# Fleet-Monitor-Overview.net
KiCad netlist of a schematic drawn in Altium Designer
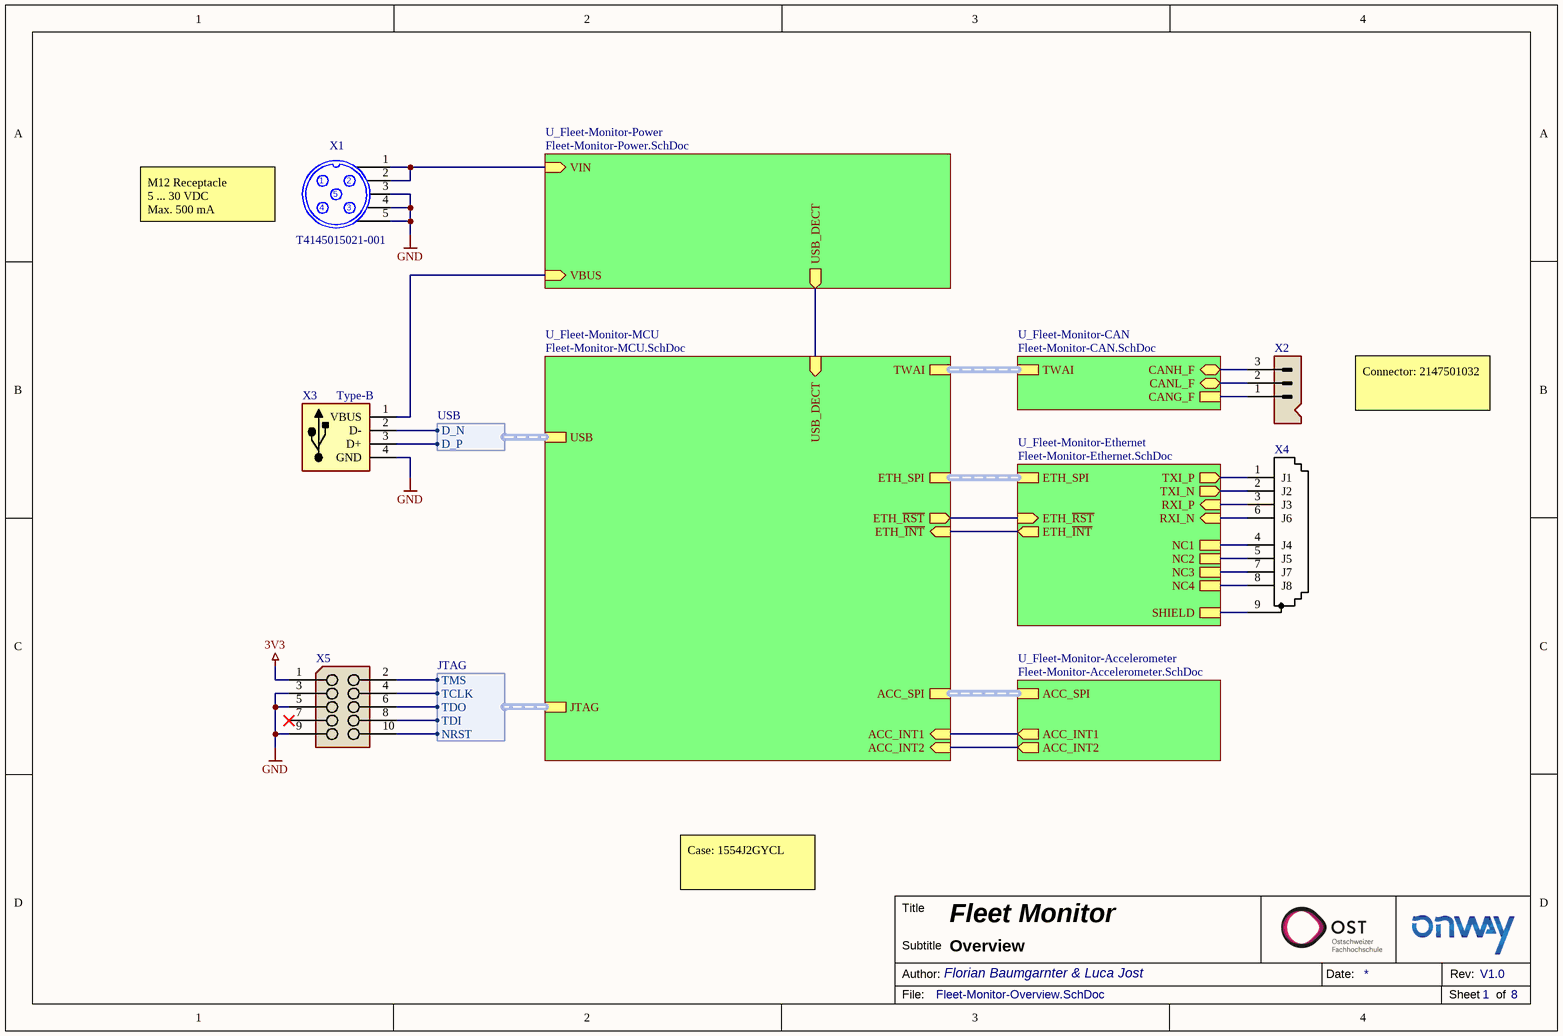
[diagram p0: Fleet-Monitor-Overview.SchDoc]

(export (version "E")
  (design (tool "Eeschema 10.0.6"))
  (components
    (comp (ref "X1")
      (value "T4145015021-001")
      (footprint "THT Connector M12")
      (description "M12 Receptacle Connector PCB Assembly")
      (libsource (lib "Fleet-Monitor") (part "T4145015021"))
    )
    (comp (ref "X2")
      (value "Pin Header Through Hole Wire To Board")
      (footprint "THT Connector 0436500315")
      (libsource (lib "Fleet-Monitor") (part "X-Stiftleiste (3-Fach)"))
    )
    (comp (ref "X3")
      (value "Type-B")
      (footprint "THT Connector MUSBD111M5")
      (description "Typ-B")
      (libsource (lib "Fleet-Monitor") (part "X-USB-Buchse"))
    )
    (comp (ref "X4")
      (value "NE8FDH-C5E-TOP")
      (footprint "THT Connector NE8FDH-C5E-TOP")
      (description "RJ45 etherCON IP65")
      (libsource (lib "Fleet-Monitor") (part "NE8FDH-C5E-TOP"))
    )
    (comp (ref "X5")
      (value "JTAG-Header (ARM-Cortex)")
      (footprint "SMD Connector 1.27mm (2x5)")
      (libsource (lib "Custom ST-Link Old") (part "X-JTAG-Header (ARM-Cortex)"))
    )
  )
  (nets
    (net (code "6") (name "/CANG_F") (class "Default")
      (node (ref "X2") (pin "1") (pinfunction "1_1") (pintype "passive"))
    )
    (net (code "7") (name "/CANH_F") (class "Default")
      (node (ref "X2") (pin "3") (pinfunction "1_3") (pintype "passive"))
    )
    (net (code "8") (name "/CANL_F") (class "Default")
      (node (ref "X2") (pin "2") (pinfunction "2_2") (pintype "passive"))
    )
    (net (code "9") (name "/D_N") (class "Default")
      (node (ref "X3") (pin "2") (pinfunction "D-_2") (pintype "passive"))
    )
    (net (code "10") (name "/D_P") (class "Default")
      (node (ref "X3") (pin "3") (pinfunction "D+_3") (pintype "passive"))
    )
    (net (code "14") (name "/NC1") (class "Default")
      (node (ref "X4") (pin "4") (pinfunction "4_4") (pintype "passive"))
    )
    (net (code "15") (name "/NC2") (class "Default")
      (node (ref "X4") (pin "5") (pinfunction "5_5") (pintype "passive"))
    )
    (net (code "16") (name "/NC3") (class "Default")
      (node (ref "X4") (pin "7") (pinfunction "7_7") (pintype "passive"))
    )
    (net (code "17") (name "/NC4") (class "Default")
      (node (ref "X4") (pin "8") (pinfunction "8_8") (pintype "passive"))
    )
    (net (code "18") (name "/NRST") (class "Default")
      (node (ref "X5") (pin "10") (pinfunction "10_10") (pintype "passive"))
    )
    (net (code "19") (name "/RXI_N") (class "Default")
      (node (ref "X4") (pin "6") (pinfunction "6_6") (pintype "passive"))
    )
    (net (code "20") (name "/RXI_P") (class "Default")
      (node (ref "X4") (pin "3") (pinfunction "3_3") (pintype "passive"))
    )
    (net (code "21") (name "/SHIELD") (class "Default")
      (node (ref "X4") (pin "9") (pinfunction "9_9") (pintype "passive"))
    )
    (net (code "22") (name "/TCLK") (class "Default")
      (node (ref "X5") (pin "4") (pinfunction "4_4") (pintype "passive"))
    )
    (net (code "23") (name "/TDI") (class "Default")
      (node (ref "X5") (pin "8") (pinfunction "8_8") (pintype "passive"))
    )
    (net (code "24") (name "/TDO") (class "Default")
      (node (ref "X5") (pin "6") (pinfunction "6_6") (pintype "passive"))
    )
    (net (code "25") (name "/TMS") (class "Default")
      (node (ref "X5") (pin "2") (pinfunction "2_2") (pintype "passive"))
    )
    (net (code "27") (name "/TXI_N") (class "Default")
      (node (ref "X4") (pin "2") (pinfunction "2_2") (pintype "passive"))
    )
    (net (code "28") (name "/TXI_P") (class "Default")
      (node (ref "X4") (pin "1") (pinfunction "1_1") (pintype "passive"))
    )
    (net (code "30") (name "/VBUS") (class "Default")
      (node (ref "X3") (pin "1") (pinfunction "VBUS_1") (pintype "passive"))
    )
    (net (code "31") (name "/VIN") (class "Default")
      (node (ref "X1") (pin "1") (pinfunction "1_1") (pintype "passive"))
      (node (ref "X1") (pin "2") (pinfunction "2_2") (pintype "passive"))
    )
    (net (code "34") (name "3V3") (class "Default")
      (node (ref "X5") (pin "1") (pinfunction "1_1") (pintype "passive"))
    )
    (net (code "35") (name "GND") (class "Default")
      (node (ref "X1") (pin "3") (pinfunction "3_3") (pintype "passive"))
      (node (ref "X1") (pin "4") (pinfunction "4_4") (pintype "passive"))
      (node (ref "X1") (pin "5") (pinfunction "5_5") (pintype "passive"))
      (node (ref "X3") (pin "4") (pinfunction "GND_4") (pintype "passive"))
      (node (ref "X5") (pin "3") (pinfunction "3_3") (pintype "passive"))
      (node (ref "X5") (pin "5") (pinfunction "5_5") (pintype "passive"))
      (node (ref "X5") (pin "9") (pinfunction "9_9") (pintype "passive"))
    )
    (net (code "36") (name "unconnected-(X5-Pad7)") (class "Default")
      (node (ref "X5") (pin "7") (pinfunction "7_7") (pintype "passive+no_connect"))
    )
  )
)
